# ETH-PHY.net
KiCad netlist of a schematic drawn in Altium Designer
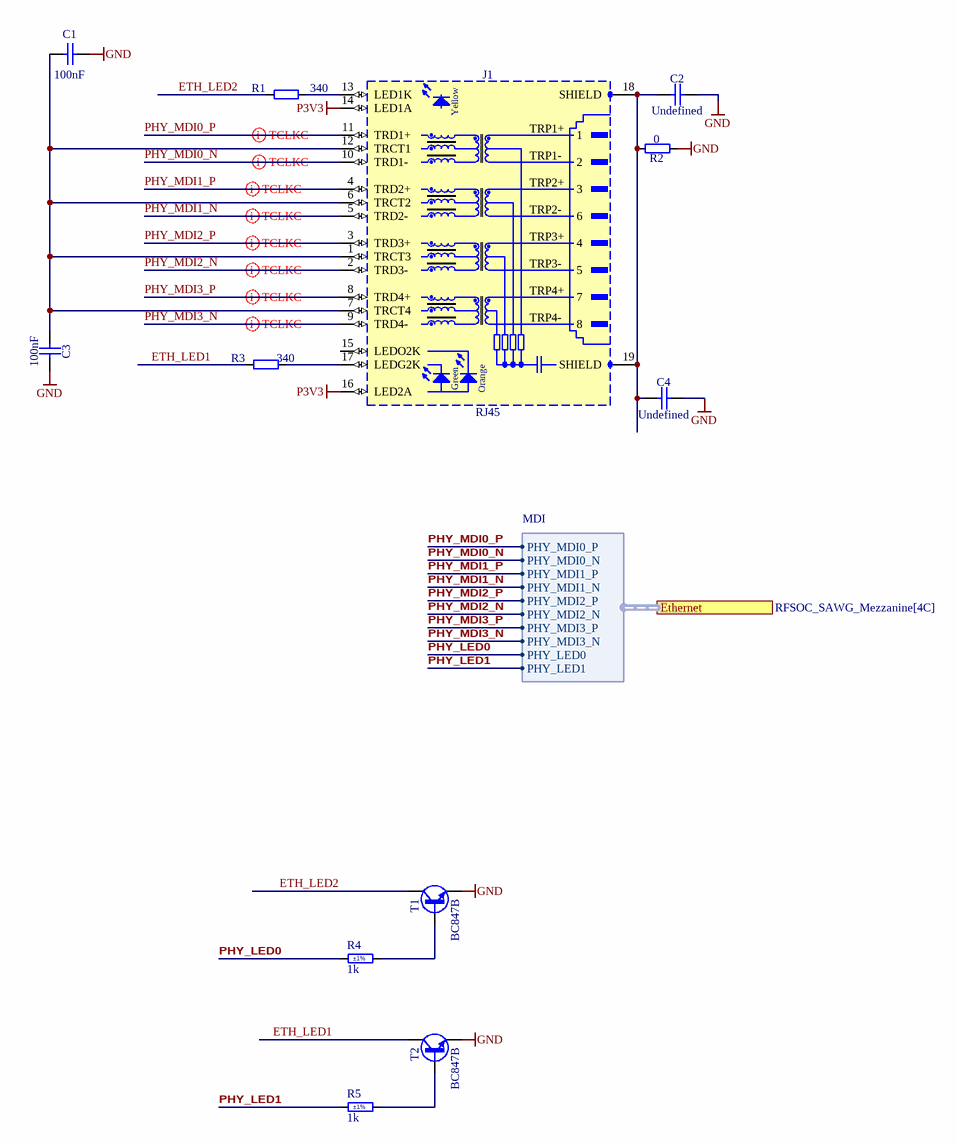
[diagram p0: ETH-PHY.SchDoc]

(export (version "E")
  (design (tool "Eeschema 10.0.6"))
  (components
    (comp (ref "C1")
      (value "100nF")
      (footprint "CAPC1005X55N")
      (description "Non-polarised capacitor")
      (fields
        (field (name "PART NUMBER") "CC0402_100NF_16V_10%_X5R")
        (field (name "VOLTAGE") "16V")
        (field (name "AUTHOR") "CERN DEM JLC")
      )
      (libsource (lib "Capacitors") (part "Capacitor - non polarized"))
    )
    (comp (ref "C2")
      (value "Undefined")
      (footprint "CAPC1608X90N")
      (description "Non-polarised capacitor")
      (fields (field (name "PART NUMBER") "CC0603_NO-VALUE") (field (name "AUTHOR") "CERN DEM MR"))
      (libsource (lib "Capacitors") (part "Capacitor - non polarized"))
    )
    (comp (ref "C3")
      (value "100nF")
      (footprint "CAPC1005X55N")
      (description "Non-polarised capacitor")
      (fields
        (field (name "PART NUMBER") "CC0402_100NF_16V_10%_X5R")
        (field (name "VOLTAGE") "16V")
        (field (name "AUTHOR") "CERN DEM JLC")
      )
      (libsource (lib "Capacitors") (part "Capacitor - non polarized"))
    )
    (comp (ref "C4")
      (value "Undefined")
      (footprint "CAPC1608X90N")
      (description "Non-polarised capacitor")
      (fields (field (name "PART NUMBER") "CC0603_NO-VALUE") (field (name "AUTHOR") "CERN DEM MR"))
      (libsource (lib "Capacitors") (part "Capacitor - non polarized"))
    )
    (comp (ref "J1")
      (value "RJ45")
      (footprint "BEL_L829-1J1T-43")
      (description "1 Port, RJ45, Gigabit Ethernet, MagJack Connector Module With Yellow And Green/Orange LEDs")
      (fields
        (field (name "PART NUMBER") "BELFUSE_L829-1J1T-43")
        (field (name "MANUFACTURER") "BEL MAGNETIC SOLUTIONS")
        (field (name "AUTHOR") "CERN DEM JLC")
      )
      (libsource (lib "Connectors") (part "BEL_L829-1J1T-43"))
    )
    (comp (ref "R1")
      (value "340")
      (footprint "RESC1608X55N")
      (description "Resistor - 0.1%")
      (fields
        (field (name "PART NUMBER") "R0603_340R_0.1%_0.063W_10PPM")
        (field (name "POWER") "0.063W")
        (field (name "AUTHOR") "CERN DEM JLC")
      )
      (libsource (lib "Resistors") (part "Resistor - 0.1%"))
    )
    (comp (ref "R2")
      (value "0")
      (footprint "RESC1005X40N")
      (description "Resistor")
      (fields
        (field (name "PART NUMBER") "R0402_0R_JUMPER")
        (field (name "MANUFACTURER") "GENERIC")
        (field (name "AUTHOR") "CERN DEM JLC")
      )
      (libsource (lib "Resistors") (part "Resistor"))
    )
    (comp (ref "R3")
      (value "340")
      (footprint "RESC1608X55N")
      (description "Resistor - 0.1%")
      (fields
        (field (name "PART NUMBER") "R0603_340R_0.1%_0.063W_10PPM")
        (field (name "POWER") "0.063W")
        (field (name "AUTHOR") "CERN DEM JLC")
      )
      (libsource (lib "Resistors") (part "Resistor - 0.1%"))
    )
    (comp (ref "R4")
      (value "1k")
      (footprint "RESC1005X40N")
      (description "Resistor - 1%")
      (fields
        (field (name "TOLERANCE") "±1%")
        (field (name "PART NUMBER") "R0402_1K_1%_0.0625W_100PPM")
        (field (name "POWER") "0.0625W")
        (field (name "AUTHOR") "CERN DEM JLC")
      )
      (libsource (lib "Resistors") (part "Resistor - 1%"))
    )
    (comp (ref "R5")
      (value "1k")
      (footprint "RESC1005X40N")
      (description "Resistor - 1%")
      (fields
        (field (name "TOLERANCE") "±1%")
        (field (name "PART NUMBER") "R0402_1K_1%_0.0625W_100PPM")
        (field (name "POWER") "0.0625W")
        (field (name "AUTHOR") "CERN DEM JLC")
      )
      (libsource (lib "Resistors") (part "Resistor - 1%"))
    )
    (comp (ref "T1")
      (value "BC847B")
      (footprint "SOT95P230X110-3N")
      (description "NPN Transistor")
      (fields (field (name "MANUFACTURER") "NXP SEMICONDUCTORS") (field (name "AUTHOR") "CERN DEM JLC"))
      (libsource (lib "ICs And Semiconductors") (part "NPN B1 E2 C3"))
    )
    (comp (ref "T2")
      (value "BC847B")
      (footprint "SOT95P230X110-3N")
      (description "NPN Transistor")
      (fields (field (name "MANUFACTURER") "NXP SEMICONDUCTORS") (field (name "AUTHOR") "CERN DEM JLC"))
      (libsource (lib "ICs And Semiconductors") (part "NPN B1 E2 C3"))
    )
  )
  (nets
    (net (code "2") (name "/ETH_LED1") (class "Default")
      (node (ref "R3") (pin "1") (pinfunction "1_1") (pintype "passive"))
      (node (ref "T2") (pin "3") (pinfunction "C_3") (pintype "passive"))
    )
    (net (code "3") (name "/ETH_LED2") (class "Default")
      (node (ref "R1") (pin "1") (pinfunction "1_1") (pintype "passive"))
      (node (ref "T1") (pin "3") (pinfunction "C_3") (pintype "passive"))
    )
    (net (code "4") (name "/PHY_LED0") (class "Default")
      (node (ref "R4") (pin "1") (pinfunction "1_1") (pintype "passive"))
    )
    (net (code "5") (name "/PHY_LED1") (class "Default")
      (node (ref "R5") (pin "1") (pinfunction "1_1") (pintype "passive"))
    )
    (net (code "6") (name "/PHY_MDI0_N") (class "Default")
      (node (ref "J1") (pin "10") (pinfunction "TRD1-_10") (pintype "bidirectional"))
    )
    (net (code "7") (name "/PHY_MDI0_P") (class "Default")
      (node (ref "J1") (pin "11") (pinfunction "TRD1+_11") (pintype "bidirectional"))
    )
    (net (code "8") (name "/PHY_MDI1_N") (class "Default")
      (node (ref "J1") (pin "5") (pinfunction "TRD2-_5") (pintype "bidirectional"))
    )
    (net (code "9") (name "/PHY_MDI1_P") (class "Default")
      (node (ref "J1") (pin "4") (pinfunction "TRD2+_4") (pintype "bidirectional"))
    )
    (net (code "10") (name "/PHY_MDI2_N") (class "Default")
      (node (ref "J1") (pin "2") (pinfunction "TRD3-_2") (pintype "bidirectional"))
    )
    (net (code "11") (name "/PHY_MDI2_P") (class "Default")
      (node (ref "J1") (pin "3") (pinfunction "TRD3+_3") (pintype "bidirectional"))
    )
    (net (code "12") (name "/PHY_MDI3_N") (class "Default")
      (node (ref "J1") (pin "9") (pinfunction "TRD4-_9") (pintype "bidirectional"))
    )
    (net (code "13") (name "/PHY_MDI3_P") (class "Default")
      (node (ref "J1") (pin "8") (pinfunction "TRD4+_8") (pintype "bidirectional"))
    )
    (net (code "15") (name "GND") (class "Default")
      (node (ref "C1") (pin "2") (pinfunction "2_2") (pintype "passive"))
      (node (ref "C2") (pin "2") (pinfunction "2_2") (pintype "passive"))
      (node (ref "C3") (pin "1") (pinfunction "1_1") (pintype "passive"))
      (node (ref "C4") (pin "2") (pinfunction "2_2") (pintype "passive"))
      (node (ref "R2") (pin "1") (pinfunction "1_1") (pintype "passive"))
      (node (ref "T1") (pin "2") (pinfunction "E_2") (pintype "passive"))
      (node (ref "T2") (pin "2") (pinfunction "E_2") (pintype "passive"))
    )
    (net (code "16") (name "Net-(C2-Pad1)") (class "Default")
      (node (ref "C2") (pin "1") (pinfunction "1_1") (pintype "passive"))
      (node (ref "C4") (pin "1") (pinfunction "1_1") (pintype "passive"))
      (node (ref "J1") (pin "18") (pinfunction "SHIELD_18") (pintype "power_in"))
      (node (ref "J1") (pin "19") (pinfunction "SHIELD_19") (pintype "power_in"))
      (node (ref "R2") (pin "2") (pinfunction "2_2") (pintype "passive"))
    )
    (net (code "17") (name "Net-(J1-LED1K)") (class "Default")
      (node (ref "J1") (pin "13") (pinfunction "LED1K_13") (pintype "bidirectional"))
      (node (ref "R1") (pin "2") (pinfunction "2_2") (pintype "passive"))
    )
    (net (code "18") (name "Net-(J1-LEDG2K)") (class "Default")
      (node (ref "J1") (pin "17") (pinfunction "LEDG2K_17") (pintype "bidirectional"))
      (node (ref "R3") (pin "2") (pinfunction "2_2") (pintype "passive"))
    )
    (net (code "19") (name "Net-(J1-TRCT1)") (class "Default")
      (node (ref "C1") (pin "1") (pinfunction "1_1") (pintype "passive"))
      (node (ref "C3") (pin "2") (pinfunction "2_2") (pintype "passive"))
      (node (ref "J1") (pin "1") (pinfunction "TRCT3_1") (pintype "bidirectional"))
      (node (ref "J1") (pin "12") (pinfunction "TRCT1_12") (pintype "bidirectional"))
      (node (ref "J1") (pin "6") (pinfunction "TRCT2_6") (pintype "bidirectional"))
      (node (ref "J1") (pin "7") (pinfunction "TRCT4_7") (pintype "bidirectional"))
    )
    (net (code "20") (name "Net-(T1-B)") (class "Default")
      (node (ref "R4") (pin "2") (pinfunction "2_2") (pintype "passive"))
      (node (ref "T1") (pin "1") (pinfunction "B_1") (pintype "passive"))
    )
    (net (code "21") (name "Net-(T2-B)") (class "Default")
      (node (ref "R5") (pin "2") (pinfunction "2_2") (pintype "passive"))
      (node (ref "T2") (pin "1") (pinfunction "B_1") (pintype "passive"))
    )
    (net (code "22") (name "P3V3") (class "Default")
      (node (ref "J1") (pin "14") (pinfunction "LED1A_14") (pintype "bidirectional"))
      (node (ref "J1") (pin "16") (pinfunction "LED2A_16") (pintype "bidirectional"))
    )
    (net (code "23") (name "unconnected-(J1-LEDO2K-Pad15)") (class "Default")
      (node (ref "J1") (pin "15") (pinfunction "LEDO2K_15") (pintype "bidirectional"))
    )
  )
)
